# SenseRing.net
KiCad netlist of a schematic drawn in EAGLE
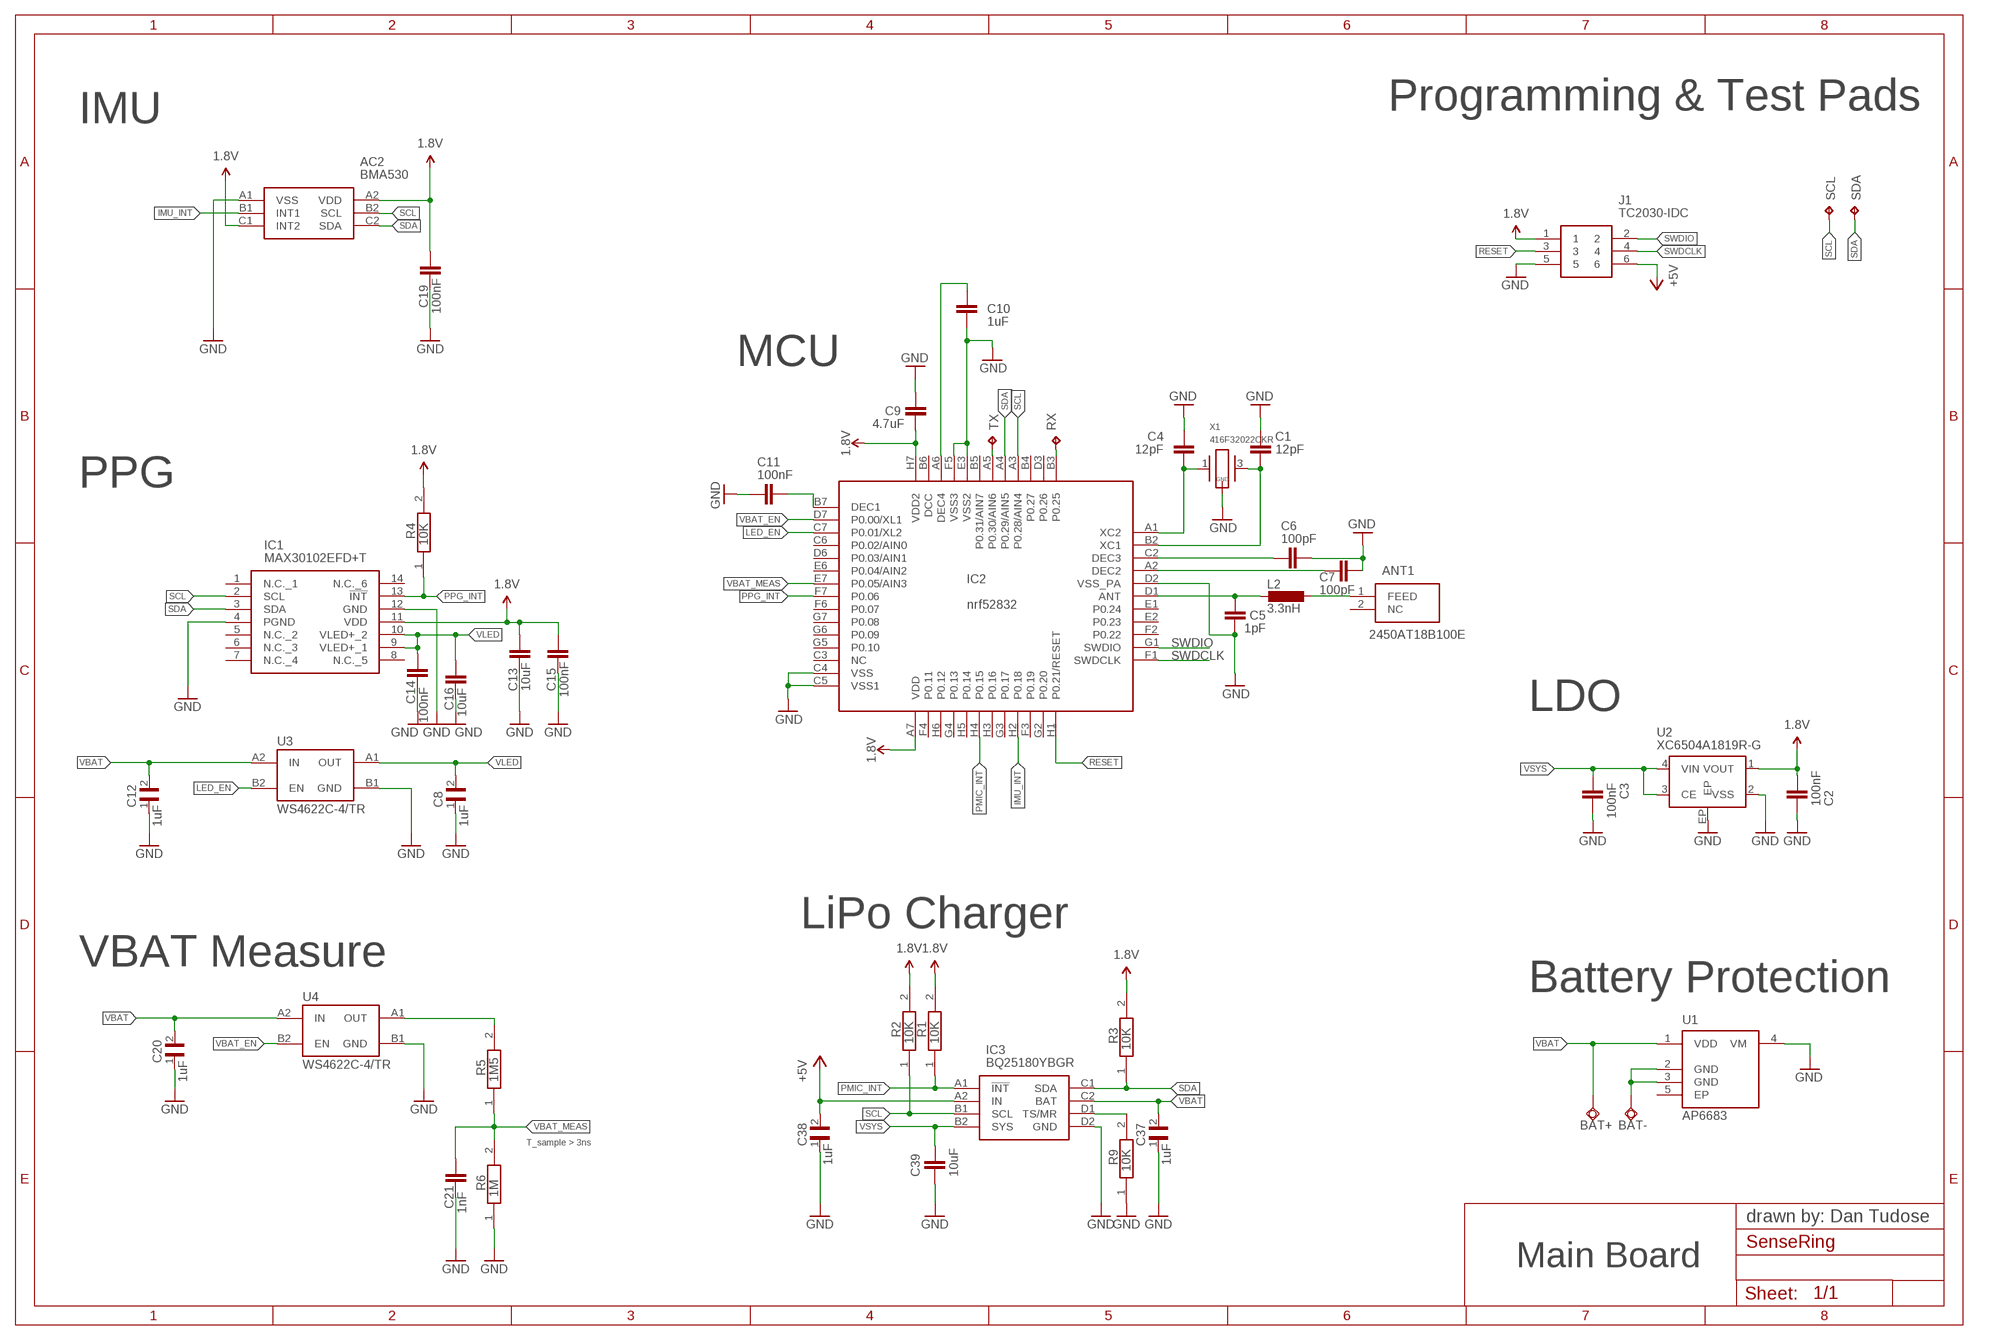
[diagram p0: schematic, sheet 1]

(export (version "E")
  (design (tool "Eeschema 10.0.6"))
  (components
    (comp (ref "AC2")
      (value "BMA530")
      (footprint "eagle-import:BMA530")
      (fields (field (name "MOUSER_PART_NUMBER") "262-BMA530"))
      (libsource (lib "eagle-import") (part "BMA530"))
    )
    (comp (ref "ANT1")
      (value "2450AT18B100E")
      (footprint "eagle-import:ANTC3216X140N")
      (fields (field (name "MOUSER_PART_NUMBER") "609-2450AT18B100E"))
      (libsource (lib "eagle-import") (part "2450AT18B100E"))
    )
    (comp (ref "BAT+")
      (value "TPSQTP10SQ")
      (footprint "eagle-import:TP10SQ")
      (libsource (lib "eagle-import") (part "TPSQTP10SQ"))
    )
    (comp (ref "BAT-")
      (value "TPSQTP10SQ")
      (footprint "eagle-import:TP10SQ")
      (libsource (lib "eagle-import") (part "TPSQTP10SQ"))
    )
    (comp (ref "C1")
      (value "12pF")
      (footprint "eagle-import:C0201")
      (libsource (lib "eagle-import") (part "C-EUC0201"))
    )
    (comp (ref "C2")
      (value "100nF")
      (footprint "eagle-import:C0201")
      (libsource (lib "eagle-import") (part "C-EUC0201"))
    )
    (comp (ref "C3")
      (value "100nF")
      (footprint "eagle-import:C0201")
      (libsource (lib "eagle-import") (part "C-EUC0201"))
    )
    (comp (ref "C4")
      (value "12pF")
      (footprint "eagle-import:C0201")
      (libsource (lib "eagle-import") (part "C-EUC0201"))
    )
    (comp (ref "C5")
      (value "1pF")
      (footprint "eagle-import:C0201")
      (libsource (lib "eagle-import") (part "rcl_vf.c4OqgsJrQZ6_cV0XoXfmAQ_C-EUC0201"))
    )
    (comp (ref "C6")
      (value "100pF")
      (footprint "eagle-import:C0201")
      (libsource (lib "eagle-import") (part "rcl_vf.c4OqgsJrQZ6_cV0XoXfmAQ_C-EUC0201"))
    )
    (comp (ref "C7")
      (value "100pF")
      (footprint "eagle-import:C0201")
      (libsource (lib "eagle-import") (part "C-EUC0201"))
    )
    (comp (ref "C8")
      (value "1uF")
      (footprint "eagle-import:0201")
      (fields (field (name "SPICEPREFIX") "C"))
      (libsource (lib "eagle-import") (part "GRM011R60J152KE01L"))
    )
    (comp (ref "C9")
      (value "4.7uF")
      (footprint "eagle-import:C0201")
      (libsource (lib "eagle-import") (part "rcl_vf.c4OqgsJrQZ6_cV0XoXfmAQ_C-EUC0201"))
    )
    (comp (ref "C10")
      (value "1uF")
      (footprint "eagle-import:C0201")
      (libsource (lib "eagle-import") (part "C-EUC0201"))
    )
    (comp (ref "C11")
      (value "100nF")
      (footprint "eagle-import:C0201")
      (libsource (lib "eagle-import") (part "rcl_vf.c4OqgsJrQZ6_cV0XoXfmAQ_C-EUC0201"))
    )
    (comp (ref "C12")
      (value "1uF")
      (footprint "eagle-import:0201")
      (fields (field (name "SPICEPREFIX") "C"))
      (libsource (lib "eagle-import") (part "GRM011R60J152KE01L"))
    )
    (comp (ref "C13")
      (value "10uF")
      (footprint "eagle-import:0402")
      (libsource (lib "eagle-import") (part "CAP_0402"))
    )
    (comp (ref "C14")
      (value "100nF")
      (footprint "eagle-import:C0201")
      (libsource (lib "eagle-import") (part "rcl_vf.c4OqgsJrQZ6_cV0XoXfmAQ_C-EUC0201"))
    )
    (comp (ref "C15")
      (value "100nF")
      (footprint "eagle-import:C0201")
      (libsource (lib "eagle-import") (part "rcl_vf.c4OqgsJrQZ6_cV0XoXfmAQ_C-EUC0201"))
    )
    (comp (ref "C16")
      (value "10uF")
      (footprint "eagle-import:0402")
      (libsource (lib "eagle-import") (part "CAP_0402"))
    )
    (comp (ref "C19")
      (value "100nF")
      (footprint "eagle-import:C0201")
      (libsource (lib "eagle-import") (part "rcl_vf.c4OqgsJrQZ6_cV0XoXfmAQ_C-EUC0201"))
    )
    (comp (ref "C20")
      (value "1uF")
      (footprint "eagle-import:0201")
      (fields (field (name "SPICEPREFIX") "C"))
      (libsource (lib "eagle-import") (part "GRM011R60J152KE01L"))
    )
    (comp (ref "C21")
      (value "1nF")
      (footprint "eagle-import:C0201")
      (libsource (lib "eagle-import") (part "C-EUC0201"))
    )
    (comp (ref "C37")
      (value "1uF")
      (footprint "eagle-import:0201")
      (fields (field (name "SPICEPREFIX") "C"))
      (libsource (lib "eagle-import") (part "GRM011R60J152KE01L"))
    )
    (comp (ref "C38")
      (value "1uF")
      (footprint "eagle-import:0201")
      (fields (field (name "SPICEPREFIX") "C"))
      (libsource (lib "eagle-import") (part "GRM011R60J152KE01L"))
    )
    (comp (ref "C39")
      (value "10uF")
      (footprint "eagle-import:0402")
      (libsource (lib "eagle-import") (part "CAP_0402"))
    )
    (comp (ref "IC1")
      (value "MAX30102EFD+T")
      (footprint "eagle-import:MAX30102EFDT")
      (fields (field (name "MOUSER_PART_NUMBER") "700-MAX30102EFD+T"))
      (libsource (lib "eagle-import") (part "MAX30102EFD+T"))
    )
    (comp (ref "IC2")
      (value "nrf52832")
      (footprint "eagle-import:NRF52832_WLCSP")
      (libsource (lib "eagle-import") (part "NRF52832"))
    )
    (comp (ref "IC3")
      (value "BQ25180YBGR")
      (footprint "eagle-import:BGA8C40P2X4_100X155X50")
      (fields (field (name "MOUSER_PART_NUMBER") "595-BQ25180YBGR"))
      (libsource (lib "eagle-import") (part "BQ25180YBGR"))
    )
    (comp (ref "J1")
      (value "TC2030-IDC")
      (footprint "eagle-import:TC2030IDC")
      (libsource (lib "eagle-import") (part "TC2030-IDC"))
    )
    (comp (ref "L2")
      (value "3.3nH")
      (footprint "eagle-import:L0201")
      (libsource (lib "eagle-import") (part "L-EUL0201"))
    )
    (comp (ref "R1")
      (value "10K")
      (footprint "eagle-import:0201")
      (fields (field (name "SPICEPREFIX") "R"))
      (libsource (lib "eagle-import") (part "CPF0201D7K68C1"))
    )
    (comp (ref "R2")
      (value "10K")
      (footprint "eagle-import:0201")
      (fields (field (name "SPICEPREFIX") "R"))
      (libsource (lib "eagle-import") (part "CPF0201D7K68C1"))
    )
    (comp (ref "R3")
      (value "10K")
      (footprint "eagle-import:0201")
      (fields (field (name "SPICEPREFIX") "R"))
      (libsource (lib "eagle-import") (part "CPF0201D7K68C1"))
    )
    (comp (ref "R4")
      (value "10K")
      (footprint "eagle-import:0201")
      (fields (field (name "SPICEPREFIX") "R"))
      (libsource (lib "eagle-import") (part "CPF0201D7K68C1"))
    )
    (comp (ref "R5")
      (value "1M5")
      (footprint "eagle-import:0201")
      (fields (field (name "SPICEPREFIX") "R"))
      (libsource (lib "eagle-import") (part "CPF0201D7K68C1"))
    )
    (comp (ref "R6")
      (value "1M")
      (footprint "eagle-import:0201")
      (fields (field (name "SPICEPREFIX") "R"))
      (libsource (lib "eagle-import") (part "CPF0201D7K68C1"))
    )
    (comp (ref "R9")
      (value "10K")
      (footprint "eagle-import:0201")
      (fields (field (name "SPICEPREFIX") "R"))
      (libsource (lib "eagle-import") (part "CPF0201D7K68C1"))
    )
    (comp (ref "RX")
      (value "TPTP06R")
      (footprint "eagle-import:TP06R")
      (libsource (lib "eagle-import") (part "TPTP06R"))
    )
    (comp (ref "SCL")
      (value "TPTP06R")
      (footprint "eagle-import:TP06R")
      (libsource (lib "eagle-import") (part "TPTP06R"))
    )
    (comp (ref "SDA")
      (value "TPTP06R")
      (footprint "eagle-import:TP06R")
      (libsource (lib "eagle-import") (part "TPTP06R"))
    )
    (comp (ref "TX")
      (value "TPTP06R")
      (footprint "eagle-import:TP06R")
      (libsource (lib "eagle-import") (part "TPTP06R"))
    )
    (comp (ref "U1")
      (value "AP6683")
      (footprint "eagle-import:DFN-4_L1.0-W1.0-P0.65-BL-EP")
      (fields (field (name "MANUFACTURER") "ALLPOWER"))
      (libsource (lib "eagle-import") (part "AP6683"))
    )
    (comp (ref "U2")
      (value "XC6504A1819R-G")
      (footprint "eagle-import:USPQ-4B04")
      (fields (field (name "MANUFACTURER") "Torex Semiconductor Ltd"))
      (libsource (lib "eagle-import") (part "XC6504A1819R-G"))
    )
    (comp (ref "U3")
      (value "WS4622C-4/TR")
      (footprint "eagle-import:CSP-4L_1X1")
      (fields (field (name "MANUFACTURER") "WILLSEMI"))
      (libsource (lib "eagle-import") (part "WS4622C-4/TR"))
    )
    (comp (ref "U4")
      (value "WS4622C-4/TR")
      (footprint "eagle-import:CSP-4L_1X1")
      (fields (field (name "MANUFACTURER") "WILLSEMI"))
      (libsource (lib "eagle-import") (part "WS4622C-4/TR"))
    )
    (comp (ref "X1")
      (value "416F32022CKR")
      (footprint "eagle-import:M416")
      (libsource (lib "eagle-import") (part "M416F26022CKR"))
    )
  )
  (nets
    (net (code "1") (name "+5V") (class "Default")
      (node (ref "C38") (pin "2") (pinfunction "2_2") (pintype "passive"))
      (node (ref "IC3") (pin "A2") (pinfunction "IN_A2") (pintype "bidirectional"))
      (node (ref "J1") (pin "6") (pinfunction "6_6") (pintype "bidirectional"))
    )
    (net (code "2") (name "1.8V") (class "Default")
      (node (ref "AC2") (pin "A2") (pinfunction "VDD_A2") (pintype "bidirectional"))
      (node (ref "AC2") (pin "C1") (pinfunction "INT2_C1") (pintype "bidirectional"))
      (node (ref "C13") (pin "1") (pinfunction "1_1") (pintype "passive"))
      (node (ref "C15") (pin "2") (pinfunction "2_2") (pintype "passive"))
      (node (ref "C19") (pin "2") (pinfunction "2_2") (pintype "passive"))
      (node (ref "C2") (pin "1") (pinfunction "1_1") (pintype "passive"))
      (node (ref "C9") (pin "2") (pinfunction "2_2") (pintype "passive"))
      (node (ref "IC1") (pin "11") (pinfunction "VDD_11") (pintype "bidirectional"))
      (node (ref "IC2") (pin "A7") (pinfunction "VDD_A7") (pintype "bidirectional"))
      (node (ref "IC2") (pin "H7") (pinfunction "VDD2_H7") (pintype "bidirectional"))
      (node (ref "J1") (pin "1") (pinfunction "1_1") (pintype "bidirectional"))
      (node (ref "R1") (pin "2") (pinfunction "2_2") (pintype "bidirectional"))
      (node (ref "R2") (pin "2") (pinfunction "2_2") (pintype "bidirectional"))
      (node (ref "R3") (pin "2") (pinfunction "2_2") (pintype "bidirectional"))
      (node (ref "R4") (pin "2") (pinfunction "2_2") (pintype "bidirectional"))
      (node (ref "U2") (pin "1") (pinfunction "VOUT_1") (pintype "power_in"))
    )
    (net (code "3") (name "GND") (class "Default")
      (node (ref "AC2") (pin "A1") (pinfunction "VSS_A1") (pintype "bidirectional"))
      (node (ref "C1") (pin "1") (pinfunction "1_1") (pintype "passive"))
      (node (ref "C10") (pin "2") (pinfunction "2_2") (pintype "passive"))
      (node (ref "C11") (pin "2") (pinfunction "2_2") (pintype "passive"))
      (node (ref "C12") (pin "1") (pinfunction "1_1") (pintype "passive"))
      (node (ref "C13") (pin "2") (pinfunction "2_2") (pintype "passive"))
      (node (ref "C14") (pin "1") (pinfunction "1_1") (pintype "passive"))
      (node (ref "C15") (pin "1") (pinfunction "1_1") (pintype "passive"))
      (node (ref "C16") (pin "2") (pinfunction "2_2") (pintype "passive"))
      (node (ref "C19") (pin "1") (pinfunction "1_1") (pintype "passive"))
      (node (ref "C2") (pin "2") (pinfunction "2_2") (pintype "passive"))
      (node (ref "C20") (pin "1") (pinfunction "1_1") (pintype "passive"))
      (node (ref "C21") (pin "1") (pinfunction "1_1") (pintype "passive"))
      (node (ref "C3") (pin "1") (pinfunction "1_1") (pintype "passive"))
      (node (ref "C37") (pin "1") (pinfunction "1_1") (pintype "passive"))
      (node (ref "C38") (pin "1") (pinfunction "1_1") (pintype "passive"))
      (node (ref "C39") (pin "2") (pinfunction "2_2") (pintype "passive"))
      (node (ref "C4") (pin "1") (pinfunction "1_1") (pintype "passive"))
      (node (ref "C5") (pin "2") (pinfunction "2_2") (pintype "passive"))
      (node (ref "C6") (pin "2") (pinfunction "2_2") (pintype "passive"))
      (node (ref "C7") (pin "2") (pinfunction "2_2") (pintype "passive"))
      (node (ref "C8") (pin "1") (pinfunction "1_1") (pintype "passive"))
      (node (ref "C9") (pin "1") (pinfunction "1_1") (pintype "passive"))
      (node (ref "IC1") (pin "12") (pinfunction "GND_12") (pintype "bidirectional"))
      (node (ref "IC1") (pin "4") (pinfunction "PGND_4") (pintype "bidirectional"))
      (node (ref "IC2") (pin "C4") (pinfunction "VSS_C4") (pintype "bidirectional"))
      (node (ref "IC2") (pin "C5") (pinfunction "VSS1_C5") (pintype "bidirectional"))
      (node (ref "IC2") (pin "D2") (pinfunction "VSS_PA_D2") (pintype "bidirectional"))
      (node (ref "IC2") (pin "E3") (pinfunction "VSS2_E3") (pintype "bidirectional"))
      (node (ref "IC2") (pin "F5") (pinfunction "VSS3_F5") (pintype "bidirectional"))
      (node (ref "IC3") (pin "D2") (pinfunction "GND_D2") (pintype "bidirectional"))
      (node (ref "J1") (pin "5") (pinfunction "5_5") (pintype "bidirectional"))
      (node (ref "R6") (pin "1") (pinfunction "1_1") (pintype "bidirectional"))
      (node (ref "R9") (pin "1") (pinfunction "1_1") (pintype "bidirectional"))
      (node (ref "U1") (pin "4") (pinfunction "VM_4") (pintype "passive"))
      (node (ref "U2") (pin "2") (pinfunction "VSS_2") (pintype "power_in"))
      (node (ref "U2") (pin "EP") (pinfunction "EP_EP") (pintype "power_in"))
      (node (ref "U3") (pin "B1") (pinfunction "GND_B1") (pintype "power_in"))
      (node (ref "U4") (pin "B1") (pinfunction "GND_B1") (pintype "power_in"))
      (node (ref "X1") (pin "2") (pinfunction "GND_2") (pintype "bidirectional"))
      (node (ref "X1") (pin "4") (pinfunction "GND_4") (pintype "bidirectional"))
    )
    (net (code "4") (name "IMU_INT") (class "Default")
      (node (ref "AC2") (pin "B1") (pinfunction "INT1_B1") (pintype "bidirectional"))
      (node (ref "IC2") (pin "H2") (pinfunction "P0.18_H2") (pintype "bidirectional"))
    )
    (net (code "5") (name "LED_EN") (class "Default")
      (node (ref "IC2") (pin "C7") (pinfunction "P0.01/XL2_C7") (pintype "bidirectional"))
      (node (ref "U3") (pin "B2") (pinfunction "EN_B2") (pintype "input"))
    )
    (net (code "6") (name "Net-(ANT1-FEED)") (class "Default")
      (node (ref "ANT1") (pin "1") (pinfunction "FEED_1") (pintype "input"))
      (node (ref "L2") (pin "1") (pinfunction "1_1") (pintype "passive"))
    )
    (net (code "7") (name "Net-(BAT--PadTP)") (class "Default")
      (node (ref "BAT-") (pin "TP") (pinfunction "TP_TP") (pintype "input"))
      (node (ref "U1") (pin "2") (pinfunction "GND_2") (pintype "power_in"))
      (node (ref "U1") (pin "3") (pinfunction "GND_3") (pintype "power_in"))
    )
    (net (code "8") (name "Net-(IC2-ANT)") (class "Default")
      (node (ref "C5") (pin "1") (pinfunction "1_1") (pintype "passive"))
      (node (ref "IC2") (pin "D1") (pinfunction "ANT_D1") (pintype "bidirectional"))
      (node (ref "L2") (pin "2") (pinfunction "2_2") (pintype "passive"))
    )
    (net (code "9") (name "Net-(IC2-DEC1)") (class "Default")
      (node (ref "C11") (pin "1") (pinfunction "1_1") (pintype "passive"))
      (node (ref "IC2") (pin "B7") (pinfunction "DEC1_B7") (pintype "bidirectional"))
    )
    (net (code "10") (name "Net-(IC2-DEC2)") (class "Default")
      (node (ref "C7") (pin "1") (pinfunction "1_1") (pintype "passive"))
      (node (ref "IC2") (pin "A2") (pinfunction "DEC2_A2") (pintype "bidirectional"))
    )
    (net (code "11") (name "Net-(IC2-DEC3)") (class "Default")
      (node (ref "C6") (pin "1") (pinfunction "1_1") (pintype "passive"))
      (node (ref "IC2") (pin "C2") (pinfunction "DEC3_C2") (pintype "bidirectional"))
    )
    (net (code "12") (name "Net-(IC2-DEC4)") (class "Default")
      (node (ref "C10") (pin "1") (pinfunction "1_1") (pintype "passive"))
      (node (ref "IC2") (pin "A6") (pinfunction "DEC4_A6") (pintype "bidirectional"))
    )
    (net (code "13") (name "Net-(IC2-P0.25)") (class "Default")
      (node (ref "IC2") (pin "B3") (pinfunction "P0.25_B3") (pintype "bidirectional"))
      (node (ref "RX") (pin "TP") (pinfunction "TP_TP") (pintype "input"))
    )
    (net (code "14") (name "Net-(IC2-P0.30{slash}AIN6)") (class "Default")
      (node (ref "IC2") (pin "A5") (pinfunction "P0.30/AIN6_A5") (pintype "bidirectional"))
      (node (ref "TX") (pin "TP") (pinfunction "TP_TP") (pintype "input"))
    )
    (net (code "15") (name "Net-(IC2-XC1)") (class "Default")
      (node (ref "C1") (pin "2") (pinfunction "2_2") (pintype "passive"))
      (node (ref "IC2") (pin "B2") (pinfunction "XC1_B2") (pintype "bidirectional"))
      (node (ref "X1") (pin "3") (pinfunction "2_3") (pintype "bidirectional"))
    )
    (net (code "16") (name "Net-(IC2-XC2)") (class "Default")
      (node (ref "C4") (pin "2") (pinfunction "2_2") (pintype "passive"))
      (node (ref "IC2") (pin "A1") (pinfunction "XC2_A1") (pintype "bidirectional"))
      (node (ref "X1") (pin "1") (pinfunction "1_1") (pintype "bidirectional"))
    )
    (net (code "17") (name "Net-(IC3-TS{slash}MR)") (class "Default")
      (node (ref "IC3") (pin "D1") (pinfunction "TS/MR_D1") (pintype "bidirectional"))
      (node (ref "R9") (pin "2") (pinfunction "2_2") (pintype "bidirectional"))
    )
    (net (code "18") (name "Net-(U4-OUT)") (class "Default")
      (node (ref "R5") (pin "2") (pinfunction "2_2") (pintype "bidirectional"))
      (node (ref "U4") (pin "A1") (pinfunction "OUT_A1") (pintype "output"))
    )
    (net (code "19") (name "PMIC_INT") (class "Default")
      (node (ref "IC2") (pin "H4") (pinfunction "P0.15_H4") (pintype "bidirectional"))
      (node (ref "IC3") (pin "A1") (pinfunction "~{INT}_A1") (pintype "bidirectional"))
      (node (ref "R1") (pin "1") (pinfunction "1_1") (pintype "bidirectional"))
    )
    (net (code "20") (name "PPG_INT") (class "Default")
      (node (ref "IC1") (pin "13") (pinfunction "~{INT}_13") (pintype "bidirectional"))
      (node (ref "IC2") (pin "F7") (pinfunction "P0.06_F7") (pintype "bidirectional"))
      (node (ref "R4") (pin "1") (pinfunction "1_1") (pintype "bidirectional"))
    )
    (net (code "21") (name "RESET") (class "Default")
      (node (ref "IC2") (pin "H1") (pinfunction "P0.21/RESET_H1") (pintype "bidirectional"))
      (node (ref "J1") (pin "3") (pinfunction "3_3") (pintype "bidirectional"))
    )
    (net (code "22") (name "SCL") (class "Default")
      (node (ref "AC2") (pin "B2") (pinfunction "SCL_B2") (pintype "bidirectional"))
      (node (ref "IC1") (pin "2") (pinfunction "SCL_2") (pintype "bidirectional"))
      (node (ref "IC2") (pin "A3") (pinfunction "P0.28/AIN4_A3") (pintype "bidirectional"))
      (node (ref "IC3") (pin "B1") (pinfunction "SCL_B1") (pintype "bidirectional"))
      (node (ref "R2") (pin "1") (pinfunction "1_1") (pintype "bidirectional"))
      (node (ref "SCL") (pin "TP") (pinfunction "TP_TP") (pintype "input"))
    )
    (net (code "23") (name "SDA") (class "Default")
      (node (ref "AC2") (pin "C2") (pinfunction "SDA_C2") (pintype "bidirectional"))
      (node (ref "IC1") (pin "3") (pinfunction "SDA_3") (pintype "bidirectional"))
      (node (ref "IC2") (pin "A4") (pinfunction "P0.29/AIN5_A4") (pintype "bidirectional"))
      (node (ref "IC3") (pin "C1") (pinfunction "SDA_C1") (pintype "bidirectional"))
      (node (ref "R3") (pin "1") (pinfunction "1_1") (pintype "bidirectional"))
      (node (ref "SDA") (pin "TP") (pinfunction "TP_TP") (pintype "input"))
    )
    (net (code "24") (name "SWDCLK") (class "Default")
      (node (ref "IC2") (pin "F1") (pinfunction "SWDCLK_F1") (pintype "bidirectional"))
      (node (ref "J1") (pin "4") (pinfunction "4_4") (pintype "bidirectional"))
    )
    (net (code "25") (name "SWDIO") (class "Default")
      (node (ref "IC2") (pin "G1") (pinfunction "SWDIO_G1") (pintype "bidirectional"))
      (node (ref "J1") (pin "2") (pinfunction "2_2") (pintype "bidirectional"))
    )
    (net (code "26") (name "VBAT") (class "Default")
      (node (ref "BAT+") (pin "TP") (pinfunction "TP_TP") (pintype "input"))
      (node (ref "C12") (pin "2") (pinfunction "2_2") (pintype "passive"))
      (node (ref "C20") (pin "2") (pinfunction "2_2") (pintype "passive"))
      (node (ref "C37") (pin "2") (pinfunction "2_2") (pintype "passive"))
      (node (ref "IC3") (pin "C2") (pinfunction "BAT_C2") (pintype "bidirectional"))
      (node (ref "U1") (pin "1") (pinfunction "VDD_1") (pintype "power_in"))
      (node (ref "U3") (pin "A2") (pinfunction "IN_A2") (pintype "input"))
      (node (ref "U4") (pin "A2") (pinfunction "IN_A2") (pintype "input"))
    )
    (net (code "27") (name "VBAT_EN") (class "Default")
      (node (ref "IC2") (pin "D7") (pinfunction "P0.00/XL1_D7") (pintype "bidirectional"))
      (node (ref "U4") (pin "B2") (pinfunction "EN_B2") (pintype "input"))
    )
    (net (code "28") (name "VBAT_MEAS") (class "Default")
      (node (ref "C21") (pin "2") (pinfunction "2_2") (pintype "passive"))
      (node (ref "IC2") (pin "E7") (pinfunction "P0.05/AIN3_E7") (pintype "bidirectional"))
      (node (ref "R5") (pin "1") (pinfunction "1_1") (pintype "bidirectional"))
      (node (ref "R6") (pin "2") (pinfunction "2_2") (pintype "bidirectional"))
    )
    (net (code "29") (name "VLED") (class "Default")
      (node (ref "C14") (pin "2") (pinfunction "2_2") (pintype "passive"))
      (node (ref "C16") (pin "1") (pinfunction "1_1") (pintype "passive"))
      (node (ref "C8") (pin "2") (pinfunction "2_2") (pintype "passive"))
      (node (ref "IC1") (pin "10") (pinfunction "VLED+_2_10") (pintype "bidirectional"))
      (node (ref "IC1") (pin "9") (pinfunction "VLED+_1_9") (pintype "bidirectional"))
      (node (ref "U3") (pin "A1") (pinfunction "OUT_A1") (pintype "output"))
    )
    (net (code "30") (name "VSYS") (class "Default")
      (node (ref "C3") (pin "2") (pinfunction "2_2") (pintype "passive"))
      (node (ref "C39") (pin "1") (pinfunction "1_1") (pintype "passive"))
      (node (ref "IC3") (pin "B2") (pinfunction "SYS_B2") (pintype "bidirectional"))
      (node (ref "U2") (pin "3") (pinfunction "CE_3") (pintype "input"))
      (node (ref "U2") (pin "4") (pinfunction "VIN_4") (pintype "power_in"))
    )
    (net (code "31") (name "unconnected-(ANT1-NC-Pad2)") (class "Default")
      (node (ref "ANT1") (pin "2") (pinfunction "NC_2") (pintype "no_connect"))
    )
    (net (code "32") (name "unconnected-(IC1-N.C._1-Pad1)") (class "Default")
      (node (ref "IC1") (pin "1") (pinfunction "N.C._1_1") (pintype "bidirectional"))
    )
    (net (code "33") (name "unconnected-(IC1-N.C._2-Pad5)") (class "Default")
      (node (ref "IC1") (pin "5") (pinfunction "N.C._2_5") (pintype "bidirectional"))
    )
    (net (code "34") (name "unconnected-(IC1-N.C._3-Pad6)") (class "Default")
      (node (ref "IC1") (pin "6") (pinfunction "N.C._3_6") (pintype "bidirectional"))
    )
    (net (code "35") (name "unconnected-(IC1-N.C._4-Pad7)") (class "Default")
      (node (ref "IC1") (pin "7") (pinfunction "N.C._4_7") (pintype "bidirectional"))
    )
    (net (code "36") (name "unconnected-(IC1-N.C._5-Pad8)") (class "Default")
      (node (ref "IC1") (pin "8") (pinfunction "N.C._5_8") (pintype "bidirectional"))
    )
    (net (code "37") (name "unconnected-(IC1-N.C._6-Pad14)") (class "Default")
      (node (ref "IC1") (pin "14") (pinfunction "N.C._6_14") (pintype "bidirectional"))
    )
    (net (code "38") (name "unconnected-(IC2-DCC-PadB6)") (class "Default")
      (node (ref "IC2") (pin "B6") (pinfunction "DCC_B6") (pintype "bidirectional"))
    )
    (net (code "39") (name "unconnected-(IC2-NC-PadC3)") (class "Default")
      (node (ref "IC2") (pin "C3") (pinfunction "NC_C3") (pintype "bidirectional"))
    )
    (net (code "40") (name "unconnected-(IC2-P0.02{slash}AIN0-PadC6)") (class "Default")
      (node (ref "IC2") (pin "C6") (pinfunction "P0.02/AIN0_C6") (pintype "bidirectional"))
    )
    (net (code "41") (name "unconnected-(IC2-P0.03{slash}AIN1-PadD6)") (class "Default")
      (node (ref "IC2") (pin "D6") (pinfunction "P0.03/AIN1_D6") (pintype "bidirectional"))
    )
    (net (code "42") (name "unconnected-(IC2-P0.04{slash}AIN2-PadE6)") (class "Default")
      (node (ref "IC2") (pin "E6") (pinfunction "P0.04/AIN2_E6") (pintype "bidirectional"))
    )
    (net (code "43") (name "unconnected-(IC2-P0.07-PadF6)") (class "Default")
      (node (ref "IC2") (pin "F6") (pinfunction "P0.07_F6") (pintype "bidirectional"))
    )
    (net (code "44") (name "unconnected-(IC2-P0.08-PadG7)") (class "Default")
      (node (ref "IC2") (pin "G7") (pinfunction "P0.08_G7") (pintype "bidirectional"))
    )
    (net (code "45") (name "unconnected-(IC2-P0.09-PadG6)") (class "Default")
      (node (ref "IC2") (pin "G6") (pinfunction "P0.09_G6") (pintype "bidirectional"))
    )
    (net (code "46") (name "unconnected-(IC2-P0.10-PadG5)") (class "Default")
      (node (ref "IC2") (pin "G5") (pinfunction "P0.10_G5") (pintype "bidirectional"))
    )
    (net (code "47") (name "unconnected-(IC2-P0.11-PadF4)") (class "Default")
      (node (ref "IC2") (pin "F4") (pinfunction "P0.11_F4") (pintype "bidirectional"))
    )
    (net (code "48") (name "unconnected-(IC2-P0.12-PadH6)") (class "Default")
      (node (ref "IC2") (pin "H6") (pinfunction "P0.12_H6") (pintype "bidirectional"))
    )
    (net (code "49") (name "unconnected-(IC2-P0.13-PadG4)") (class "Default")
      (node (ref "IC2") (pin "G4") (pinfunction "P0.13_G4") (pintype "bidirectional"))
    )
    (net (code "50") (name "unconnected-(IC2-P0.14-PadH5)") (class "Default")
      (node (ref "IC2") (pin "H5") (pinfunction "P0.14_H5") (pintype "bidirectional"))
    )
    (net (code "51") (name "unconnected-(IC2-P0.16-PadH3)") (class "Default")
      (node (ref "IC2") (pin "H3") (pinfunction "P0.16_H3") (pintype "bidirectional"))
    )
    (net (code "52") (name "unconnected-(IC2-P0.17-PadG3)") (class "Default")
      (node (ref "IC2") (pin "G3") (pinfunction "P0.17_G3") (pintype "bidirectional"))
    )
    (net (code "53") (name "unconnected-(IC2-P0.19-PadF3)") (class "Default")
      (node (ref "IC2") (pin "F3") (pinfunction "P0.19_F3") (pintype "bidirectional"))
    )
    (net (code "54") (name "unconnected-(IC2-P0.20-PadG2)") (class "Default")
      (node (ref "IC2") (pin "G2") (pinfunction "P0.20_G2") (pintype "bidirectional"))
    )
    (net (code "55") (name "unconnected-(IC2-P0.22-PadF2)") (class "Default")
      (node (ref "IC2") (pin "F2") (pinfunction "P0.22_F2") (pintype "bidirectional"))
    )
    (net (code "56") (name "unconnected-(IC2-P0.23-PadE2)") (class "Default")
      (node (ref "IC2") (pin "E2") (pinfunction "P0.23_E2") (pintype "bidirectional"))
    )
    (net (code "57") (name "unconnected-(IC2-P0.24-PadE1)") (class "Default")
      (node (ref "IC2") (pin "E1") (pinfunction "P0.24_E1") (pintype "bidirectional"))
    )
    (net (code "58") (name "unconnected-(IC2-P0.26-PadD3)") (class "Default")
      (node (ref "IC2") (pin "D3") (pinfunction "P0.26_D3") (pintype "bidirectional"))
    )
    (net (code "59") (name "unconnected-(IC2-P0.27-PadB4)") (class "Default")
      (node (ref "IC2") (pin "B4") (pinfunction "P0.27_B4") (pintype "bidirectional"))
    )
    (net (code "60") (name "unconnected-(IC2-P0.31{slash}AIN7-PadB5)") (class "Default")
      (node (ref "IC2") (pin "B5") (pinfunction "P0.31/AIN7_B5") (pintype "bidirectional"))
    )
    (net (code "61") (name "unconnected-(U1-EP-Pad5)") (class "Default")
      (node (ref "U1") (pin "5") (pinfunction "EP_5") (pintype "passive"))
    )
  )
)
